# p20-001.net
KiCad netlist of a schematic drawn in EAGLE
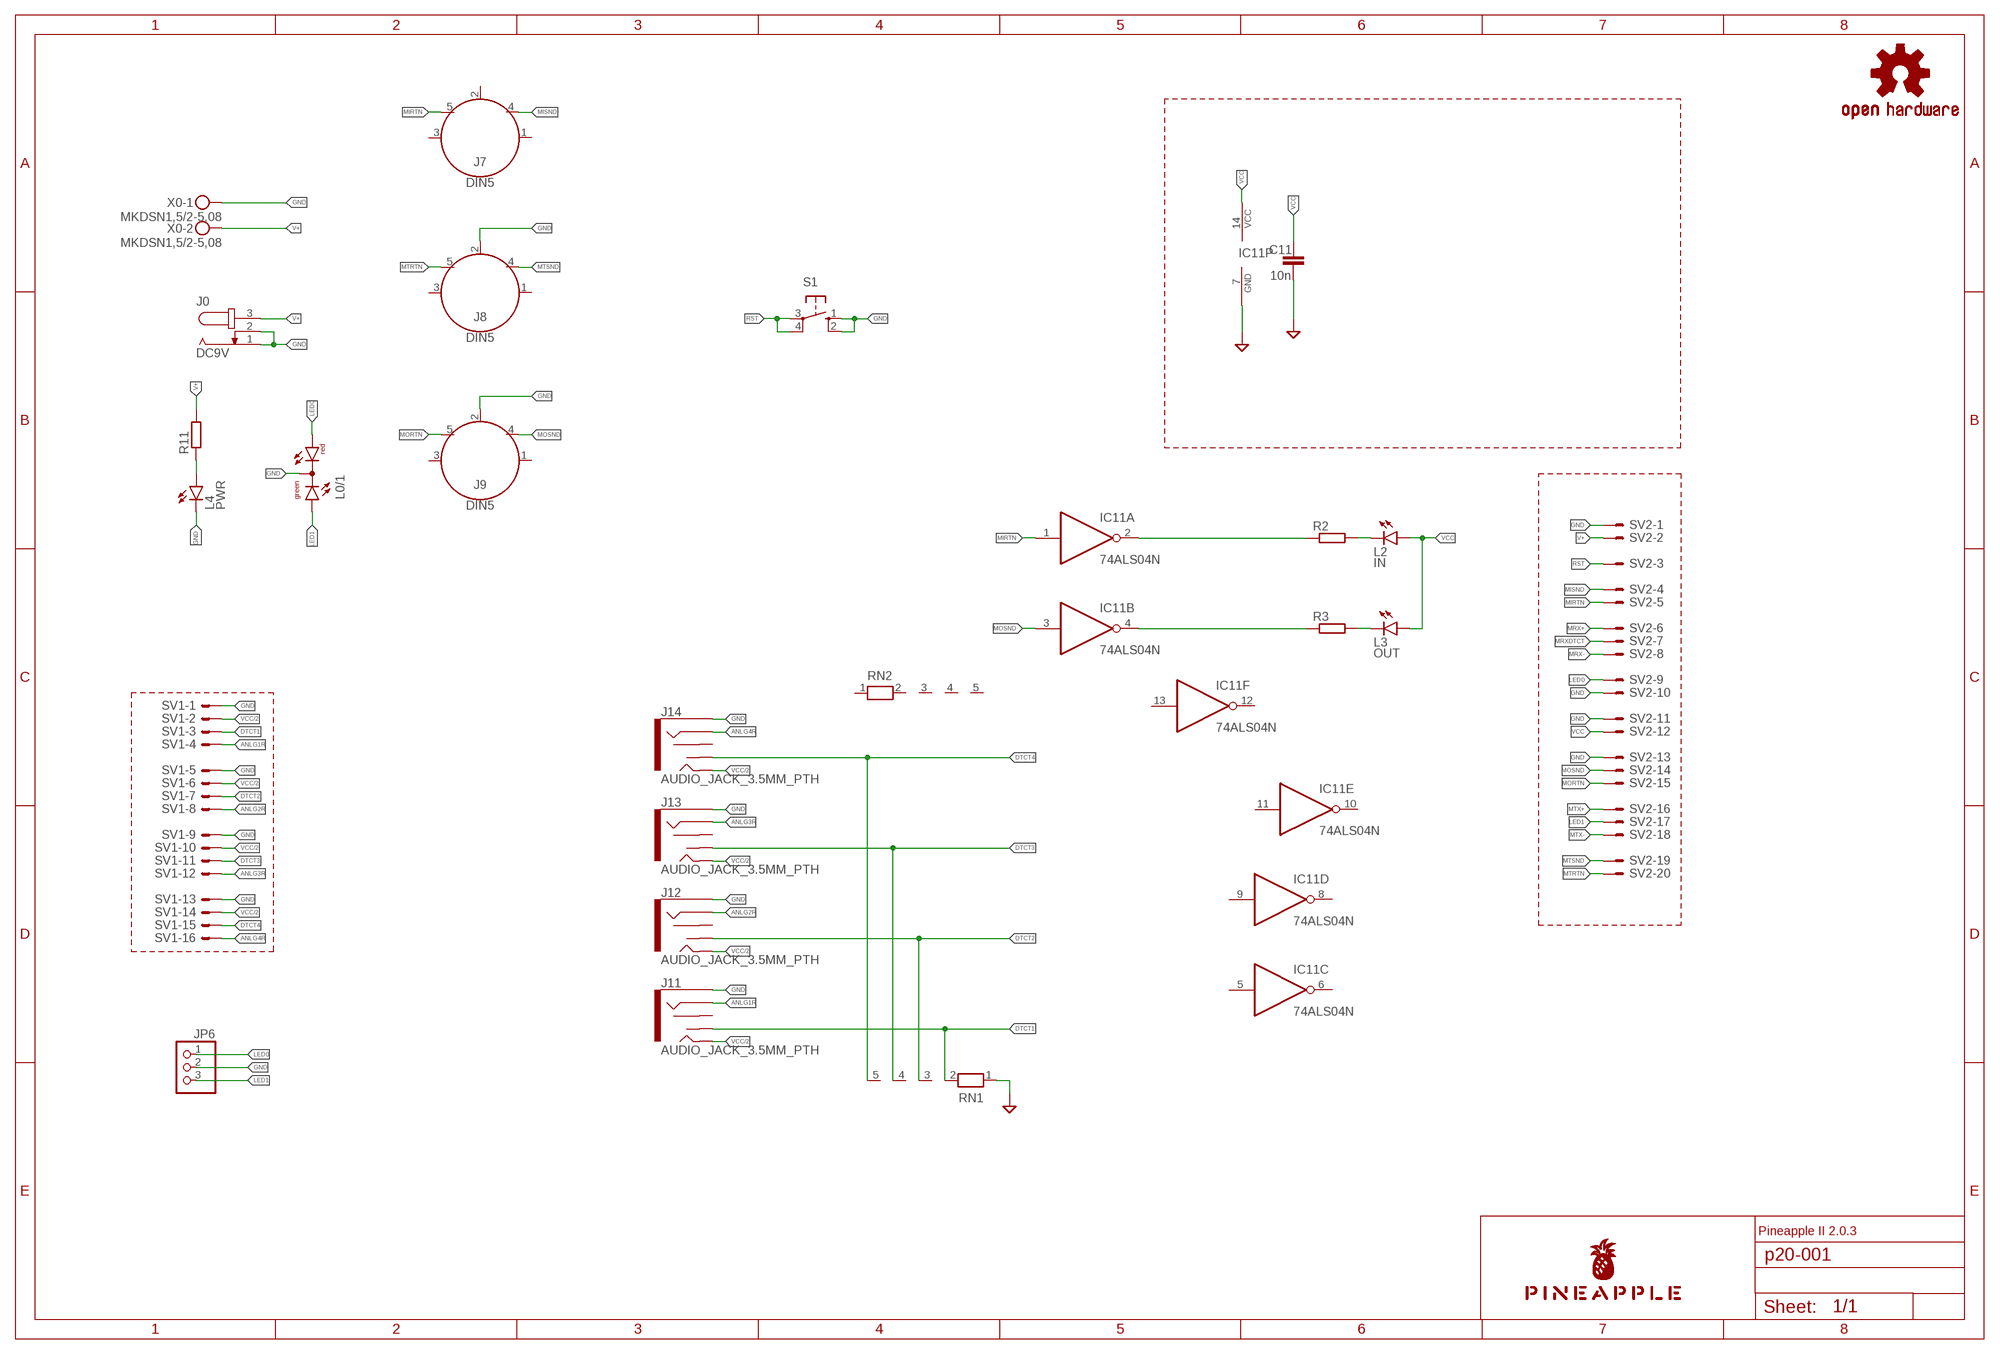
[diagram p0: schematic, sheet 1]

(export (version "E")
  (design (tool "Eeschema 10.0.6"))
  (components
    (comp (ref "C11")
      (value "10n")
      (footprint "eagle-import:C025-024X044")
      (libsource (lib "eagle-import") (part "C-EU025-024X044"))
    )
    (comp (ref "IC11")
      (value "74ALS04N")
      (footprint "eagle-import:DIL14")
      (libsource (lib "eagle-import") (part "7404NALS"))
    )
    (comp (ref "J0")
      (value "DC9V")
      (footprint "eagle-import:SPC4077")
      (libsource (lib "eagle-import") (part "JACK-PLUG0"))
    )
    (comp (ref "J7")
      (value "DIN5")
      (footprint "eagle-import:DIN5-RA-PTH")
      (libsource (lib "eagle-import") (part "DIN5"))
    )
    (comp (ref "J8")
      (value "DIN5")
      (footprint "eagle-import:DIN5-RA-PTH")
      (libsource (lib "eagle-import") (part "DIN5"))
    )
    (comp (ref "J9")
      (value "DIN5")
      (footprint "eagle-import:DIN5-RA-PTH")
      (libsource (lib "eagle-import") (part "DIN5"))
    )
    (comp (ref "J11")
      (value "AUDIO_JACK_3.5MM_PTH")
      (footprint "eagle-import:AUDIO-JACK")
      (libsource (lib "eagle-import") (part "AUDIO_JACK_3.5MM_PTH"))
    )
    (comp (ref "J12")
      (value "AUDIO_JACK_3.5MM_PTH")
      (footprint "eagle-import:AUDIO-JACK")
      (libsource (lib "eagle-import") (part "AUDIO_JACK_3.5MM_PTH"))
    )
    (comp (ref "J13")
      (value "AUDIO_JACK_3.5MM_PTH")
      (footprint "eagle-import:AUDIO-JACK")
      (libsource (lib "eagle-import") (part "AUDIO_JACK_3.5MM_PTH"))
    )
    (comp (ref "J14")
      (value "AUDIO_JACK_3.5MM_PTH")
      (footprint "eagle-import:AUDIO-JACK")
      (libsource (lib "eagle-import") (part "AUDIO_JACK_3.5MM_PTH"))
    )
    (comp (ref "JP6")
      (value "PINHD-1X3")
      (footprint "eagle-import:1X03")
      (libsource (lib "eagle-import") (part "PINHD-1X3"))
    )
    (comp (ref "L0/1")
      (value "DUOLED-RG-C")
      (footprint "eagle-import:DUOLED-C-5MM")
      (libsource (lib "eagle-import") (part "DUOLED-RG-C"))
    )
    (comp (ref "L2")
      (value "IN")
      (footprint "eagle-import:LED3MM")
      (libsource (lib "eagle-import") (part "LED3MM"))
    )
    (comp (ref "L3")
      (value "OUT")
      (footprint "eagle-import:LED3MM")
      (libsource (lib "eagle-import") (part "LED3MM"))
    )
    (comp (ref "L4")
      (value "PWR")
      (footprint "eagle-import:LED3MM")
      (libsource (lib "eagle-import") (part "LED3MM"))
    )
    (comp (ref "LOGO1")
      (value "OSHW-LOGOS-COPPER")
      (footprint "eagle-import:OSHW-LOGO-S_COPPER")
      (libsource (lib "eagle-import") (part "OSHW-LOGOS-COPPER"))
    )
    (comp (ref "R2")
      (value "R-EU_0204/5")
      (footprint "eagle-import:0204_5")
      (libsource (lib "eagle-import") (part "R-EU_0204/5"))
    )
    (comp (ref "R3")
      (value "R-EU_0204/5")
      (footprint "eagle-import:0204_5")
      (libsource (lib "eagle-import") (part "R-EU_0204/5"))
    )
    (comp (ref "R11")
      (value "R-EU_0204/5")
      (footprint "eagle-import:0204_5")
      (libsource (lib "eagle-import") (part "R-EU_0204/5"))
    )
    (comp (ref "RN1")
      (value "RN04")
      (footprint "eagle-import:RN-5")
      (libsource (lib "eagle-import") (part "RN04"))
    )
    (comp (ref "RN2")
      (value "RN04")
      (footprint "eagle-import:RN-5")
      (libsource (lib "eagle-import") (part "RN04"))
    )
    (comp (ref "S1")
      (value "10-XX")
      (footprint "eagle-import:B3F-10XX")
      (fields (field (name "MPN") "B3F-1000"))
      (libsource (lib "eagle-import") (part "10-XX"))
    )
    (comp (ref "SV1")
      (value "ML16LE")
      (footprint "eagle-import:ML16L")
      (libsource (lib "eagle-import") (part "ML16LE"))
    )
    (comp (ref "SV2")
      (value "ML20LE")
      (footprint "eagle-import:ML20L")
      (libsource (lib "eagle-import") (part "ML20LE"))
    )
    (comp (ref "U$1")
      (value "PINEAPPLE450_SILK")
      (footprint "eagle-import:PINEAPPLE450_SILK")
      (libsource (lib "eagle-import") (part "PINEAPPLE450_SILK"))
    )
    (comp (ref "X0")
      (value "MKDSN1,5/2-5,08")
      (footprint "eagle-import:MKDSN1,5_2-5,08")
      (libsource (lib "eagle-import") (part "MKDSN1,5/2-5,08"))
    )
  )
  (nets
    (net (code "1") (name "ANLG1R") (class "Default")
      (node (ref "J11") (pin "RING") (pinfunction "RING_RING") (pintype "bidirectional"))
      (node (ref "SV1") (pin "4") (pinfunction "S_4") (pintype "passive"))
    )
    (net (code "2") (name "ANLG2R") (class "Default")
      (node (ref "J12") (pin "RING") (pinfunction "RING_RING") (pintype "bidirectional"))
      (node (ref "SV1") (pin "8") (pinfunction "S_8") (pintype "passive"))
    )
    (net (code "3") (name "ANLG3R") (class "Default")
      (node (ref "J13") (pin "RING") (pinfunction "RING_RING") (pintype "bidirectional"))
      (node (ref "SV1") (pin "12") (pinfunction "S_12") (pintype "passive"))
    )
    (net (code "4") (name "ANLG4R") (class "Default")
      (node (ref "J14") (pin "RING") (pinfunction "RING_RING") (pintype "bidirectional"))
      (node (ref "SV1") (pin "16") (pinfunction "S_16") (pintype "passive"))
    )
    (net (code "5") (name "DTCT1") (class "Default")
      (node (ref "J11") (pin "TSH") (pinfunction "TSH_TSH") (pintype "bidirectional"))
      (node (ref "RN1") (pin "2") (pinfunction "2_2") (pintype "passive"))
      (node (ref "SV1") (pin "3") (pinfunction "S_3") (pintype "passive"))
    )
    (net (code "6") (name "DTCT2") (class "Default")
      (node (ref "J12") (pin "TSH") (pinfunction "TSH_TSH") (pintype "bidirectional"))
      (node (ref "RN1") (pin "3") (pinfunction "3_3") (pintype "passive"))
      (node (ref "SV1") (pin "7") (pinfunction "S_7") (pintype "passive"))
    )
    (net (code "7") (name "DTCT3") (class "Default")
      (node (ref "J13") (pin "TSH") (pinfunction "TSH_TSH") (pintype "bidirectional"))
      (node (ref "RN1") (pin "4") (pinfunction "4_4") (pintype "passive"))
      (node (ref "SV1") (pin "11") (pinfunction "S_11") (pintype "passive"))
    )
    (net (code "8") (name "DTCT4") (class "Default")
      (node (ref "J14") (pin "TSH") (pinfunction "TSH_TSH") (pintype "bidirectional"))
      (node (ref "RN1") (pin "5") (pinfunction "5_5") (pintype "passive"))
      (node (ref "SV1") (pin "15") (pinfunction "S_15") (pintype "passive"))
    )
    (net (code "9") (name "GND") (class "Default")
      (node (ref "C11") (pin "2") (pinfunction "2_2") (pintype "passive"))
      (node (ref "IC11") (pin "7") (pinfunction "GND_7") (pintype "power_in"))
      (node (ref "J0") (pin "1") (pinfunction "1_1") (pintype "passive"))
      (node (ref "J0") (pin "2") (pinfunction "2_2") (pintype "passive"))
      (node (ref "J11") (pin "SLEEVE") (pinfunction "SLEEVE_SLEEVE") (pintype "bidirectional"))
      (node (ref "J12") (pin "SLEEVE") (pinfunction "SLEEVE_SLEEVE") (pintype "bidirectional"))
      (node (ref "J13") (pin "SLEEVE") (pinfunction "SLEEVE_SLEEVE") (pintype "bidirectional"))
      (node (ref "J14") (pin "SLEEVE") (pinfunction "SLEEVE_SLEEVE") (pintype "bidirectional"))
      (node (ref "J8") (pin "2") (pinfunction "2_2") (pintype "bidirectional"))
      (node (ref "J9") (pin "2") (pinfunction "2_2") (pintype "bidirectional"))
      (node (ref "JP6") (pin "2") (pinfunction "2_2") (pintype "passive"))
      (node (ref "L0/1") (pin "C") (pinfunction "C_C") (pintype "passive"))
      (node (ref "L4") (pin "K") (pinfunction "C_K") (pintype "passive"))
      (node (ref "RN1") (pin "1") (pinfunction "1_1") (pintype "passive"))
      (node (ref "S1") (pin "1") (pinfunction "S_1") (pintype "passive"))
      (node (ref "S1") (pin "2") (pinfunction "S1_2") (pintype "passive"))
      (node (ref "SV1") (pin "1") (pinfunction "S_1") (pintype "passive"))
      (node (ref "SV1") (pin "13") (pinfunction "S_13") (pintype "passive"))
      (node (ref "SV1") (pin "5") (pinfunction "S_5") (pintype "passive"))
      (node (ref "SV1") (pin "9") (pinfunction "S_9") (pintype "passive"))
      (node (ref "SV2") (pin "1") (pinfunction "S_1") (pintype "passive"))
      (node (ref "SV2") (pin "10") (pinfunction "S_10") (pintype "passive"))
      (node (ref "SV2") (pin "11") (pinfunction "S_11") (pintype "passive"))
      (node (ref "SV2") (pin "13") (pinfunction "S_13") (pintype "passive"))
      (node (ref "X0") (pin "1") (pinfunction "KL_1") (pintype "passive"))
    )
    (net (code "10") (name "LED0") (class "Default")
      (node (ref "JP6") (pin "1") (pinfunction "1_1") (pintype "passive"))
      (node (ref "L0/1") (pin "AR") (pinfunction "AR_AR") (pintype "passive"))
      (node (ref "SV2") (pin "9") (pinfunction "S_9") (pintype "passive"))
    )
    (net (code "11") (name "LED1") (class "Default")
      (node (ref "JP6") (pin "3") (pinfunction "3_3") (pintype "passive"))
      (node (ref "L0/1") (pin "AX") (pinfunction "AG_AX") (pintype "passive"))
      (node (ref "SV2") (pin "17") (pinfunction "S_17") (pintype "passive"))
    )
    (net (code "12") (name "MIRTN") (class "Default")
      (node (ref "IC11") (pin "1") (pinfunction "I_1") (pintype "input"))
      (node (ref "J7") (pin "5") (pinfunction "5_5") (pintype "bidirectional"))
      (node (ref "SV2") (pin "5") (pinfunction "S_5") (pintype "passive"))
    )
    (net (code "13") (name "MISND") (class "Default")
      (node (ref "J7") (pin "4") (pinfunction "4_4") (pintype "bidirectional"))
      (node (ref "SV2") (pin "4") (pinfunction "S_4") (pintype "passive"))
    )
    (net (code "14") (name "MORTN") (class "Default")
      (node (ref "J9") (pin "5") (pinfunction "5_5") (pintype "bidirectional"))
      (node (ref "SV2") (pin "15") (pinfunction "S_15") (pintype "passive"))
    )
    (net (code "15") (name "MOSND") (class "Default")
      (node (ref "IC11") (pin "3") (pinfunction "I_3") (pintype "input"))
      (node (ref "J9") (pin "4") (pinfunction "4_4") (pintype "bidirectional"))
      (node (ref "SV2") (pin "14") (pinfunction "S_14") (pintype "passive"))
    )
    (net (code "16") (name "MRX+") (class "Default")
      (node (ref "SV2") (pin "6") (pinfunction "S_6") (pintype "passive"))
    )
    (net (code "17") (name "MRX-") (class "Default")
      (node (ref "SV2") (pin "8") (pinfunction "S_8") (pintype "passive"))
    )
    (net (code "18") (name "MRXDTCT") (class "Default")
      (node (ref "SV2") (pin "7") (pinfunction "S_7") (pintype "passive"))
    )
    (net (code "19") (name "MTRTN") (class "Default")
      (node (ref "J8") (pin "5") (pinfunction "5_5") (pintype "bidirectional"))
      (node (ref "SV2") (pin "20") (pinfunction "S_20") (pintype "passive"))
    )
    (net (code "20") (name "MTSND") (class "Default")
      (node (ref "J8") (pin "4") (pinfunction "4_4") (pintype "bidirectional"))
      (node (ref "SV2") (pin "19") (pinfunction "S_19") (pintype "passive"))
    )
    (net (code "21") (name "MTX+") (class "Default")
      (node (ref "SV2") (pin "16") (pinfunction "S_16") (pintype "passive"))
    )
    (net (code "22") (name "MTX-") (class "Default")
      (node (ref "SV2") (pin "18") (pinfunction "S_18") (pintype "passive"))
    )
    (net (code "23") (name "Net-(IC11A-O)") (class "Default")
      (node (ref "IC11") (pin "2") (pinfunction "O_2") (pintype "output"))
      (node (ref "R2") (pin "1") (pinfunction "1_1") (pintype "passive"))
    )
    (net (code "24") (name "Net-(IC11B-O)") (class "Default")
      (node (ref "IC11") (pin "4") (pinfunction "O_4") (pintype "output"))
      (node (ref "R3") (pin "1") (pinfunction "1_1") (pintype "passive"))
    )
    (net (code "25") (name "Net-(L2-C)") (class "Default")
      (node (ref "L2") (pin "K") (pinfunction "C_K") (pintype "passive"))
      (node (ref "R2") (pin "2") (pinfunction "2_2") (pintype "passive"))
    )
    (net (code "26") (name "Net-(L3-C)") (class "Default")
      (node (ref "L3") (pin "K") (pinfunction "C_K") (pintype "passive"))
      (node (ref "R3") (pin "2") (pinfunction "2_2") (pintype "passive"))
    )
    (net (code "27") (name "Net-(L4-PadA)") (class "Default")
      (node (ref "L4") (pin "A") (pinfunction "A_A") (pintype "passive"))
      (node (ref "R11") (pin "1") (pinfunction "1_1") (pintype "passive"))
    )
    (net (code "28") (name "RST") (class "Default")
      (node (ref "S1") (pin "3") (pinfunction "P_3") (pintype "passive"))
      (node (ref "S1") (pin "4") (pinfunction "P1_4") (pintype "passive"))
      (node (ref "SV2") (pin "3") (pinfunction "S_3") (pintype "passive"))
    )
    (net (code "29") (name "V+") (class "Default")
      (node (ref "J0") (pin "3") (pinfunction "3_3") (pintype "passive"))
      (node (ref "R11") (pin "2") (pinfunction "2_2") (pintype "passive"))
      (node (ref "SV2") (pin "2") (pinfunction "S_2") (pintype "passive"))
      (node (ref "X0") (pin "2") (pinfunction "KL_2") (pintype "passive"))
    )
    (net (code "30") (name "VCC") (class "Default")
      (node (ref "C11") (pin "1") (pinfunction "1_1") (pintype "passive"))
      (node (ref "IC11") (pin "14") (pinfunction "VCC_14") (pintype "power_in"))
      (node (ref "L2") (pin "A") (pinfunction "A_A") (pintype "passive"))
      (node (ref "L3") (pin "A") (pinfunction "A_A") (pintype "passive"))
      (node (ref "SV2") (pin "12") (pinfunction "S_12") (pintype "passive"))
    )
    (net (code "31") (name "VCC{slash}2") (class "Default")
      (node (ref "J11") (pin "TIP") (pinfunction "TIP_TIP") (pintype "bidirectional"))
      (node (ref "J12") (pin "TIP") (pinfunction "TIP_TIP") (pintype "bidirectional"))
      (node (ref "J13") (pin "TIP") (pinfunction "TIP_TIP") (pintype "bidirectional"))
      (node (ref "J14") (pin "TIP") (pinfunction "TIP_TIP") (pintype "bidirectional"))
      (node (ref "SV1") (pin "10") (pinfunction "S_10") (pintype "passive"))
      (node (ref "SV1") (pin "14") (pinfunction "S_14") (pintype "passive"))
      (node (ref "SV1") (pin "2") (pinfunction "S_2") (pintype "passive"))
      (node (ref "SV1") (pin "6") (pinfunction "S_6") (pintype "passive"))
    )
    (net (code "32") (name "unconnected-(IC11C-I-Pad5)") (class "Default")
      (node (ref "IC11") (pin "5") (pinfunction "I_5") (pintype "input"))
    )
    (net (code "33") (name "unconnected-(IC11C-O-Pad6)") (class "Default")
      (node (ref "IC11") (pin "6") (pinfunction "O_6") (pintype "output"))
    )
    (net (code "34") (name "unconnected-(IC11D-I-Pad9)") (class "Default")
      (node (ref "IC11") (pin "9") (pinfunction "I_9") (pintype "input"))
    )
    (net (code "35") (name "unconnected-(IC11D-O-Pad8)") (class "Default")
      (node (ref "IC11") (pin "8") (pinfunction "O_8") (pintype "output"))
    )
    (net (code "36") (name "unconnected-(IC11E-I-Pad11)") (class "Default")
      (node (ref "IC11") (pin "11") (pinfunction "I_11") (pintype "input"))
    )
    (net (code "37") (name "unconnected-(IC11E-O-Pad10)") (class "Default")
      (node (ref "IC11") (pin "10") (pinfunction "O_10") (pintype "output"))
    )
    (net (code "38") (name "unconnected-(IC11F-I-Pad13)") (class "Default")
      (node (ref "IC11") (pin "13") (pinfunction "I_13") (pintype "input"))
    )
    (net (code "39") (name "unconnected-(IC11F-O-Pad12)") (class "Default")
      (node (ref "IC11") (pin "12") (pinfunction "O_12") (pintype "output"))
    )
    (net (code "40") (name "unconnected-(J7-Pad1)") (class "Default")
      (node (ref "J7") (pin "1") (pinfunction "1_1") (pintype "bidirectional"))
    )
    (net (code "41") (name "unconnected-(J7-Pad2)") (class "Default")
      (node (ref "J7") (pin "2") (pinfunction "2_2") (pintype "bidirectional"))
    )
    (net (code "42") (name "unconnected-(J7-Pad3)") (class "Default")
      (node (ref "J7") (pin "3") (pinfunction "3_3") (pintype "bidirectional"))
    )
    (net (code "43") (name "unconnected-(J8-Pad1)") (class "Default")
      (node (ref "J8") (pin "1") (pinfunction "1_1") (pintype "bidirectional"))
    )
    (net (code "44") (name "unconnected-(J8-Pad3)") (class "Default")
      (node (ref "J8") (pin "3") (pinfunction "3_3") (pintype "bidirectional"))
    )
    (net (code "45") (name "unconnected-(J9-Pad1)") (class "Default")
      (node (ref "J9") (pin "1") (pinfunction "1_1") (pintype "bidirectional"))
    )
    (net (code "46") (name "unconnected-(J9-Pad3)") (class "Default")
      (node (ref "J9") (pin "3") (pinfunction "3_3") (pintype "bidirectional"))
    )
    (net (code "47") (name "unconnected-(J11-PadRSH)") (class "Default")
      (node (ref "J11") (pin "RSH") (pinfunction "RSH_RSH") (pintype "bidirectional"))
    )
    (net (code "48") (name "unconnected-(J12-PadRSH)") (class "Default")
      (node (ref "J12") (pin "RSH") (pinfunction "RSH_RSH") (pintype "bidirectional"))
    )
    (net (code "49") (name "unconnected-(J13-PadRSH)") (class "Default")
      (node (ref "J13") (pin "RSH") (pinfunction "RSH_RSH") (pintype "bidirectional"))
    )
    (net (code "50") (name "unconnected-(J14-PadRSH)") (class "Default")
      (node (ref "J14") (pin "RSH") (pinfunction "RSH_RSH") (pintype "bidirectional"))
    )
    (net (code "51") (name "unconnected-(RN2-Pad1)") (class "Default")
      (node (ref "RN2") (pin "1") (pinfunction "1_1") (pintype "passive"))
    )
    (net (code "52") (name "unconnected-(RN2-Pad2)") (class "Default")
      (node (ref "RN2") (pin "2") (pinfunction "2_2") (pintype "passive"))
    )
    (net (code "53") (name "unconnected-(RN2-Pad3)") (class "Default")
      (node (ref "RN2") (pin "3") (pinfunction "3_3") (pintype "passive"))
    )
    (net (code "54") (name "unconnected-(RN2-Pad4)") (class "Default")
      (node (ref "RN2") (pin "4") (pinfunction "4_4") (pintype "passive"))
    )
    (net (code "55") (name "unconnected-(RN2-Pad5)") (class "Default")
      (node (ref "RN2") (pin "5") (pinfunction "5_5") (pintype "passive"))
    )
  )
)
